# ARM_JTAG_Header.net
KiCad netlist of a schematic drawn in Altium Designer
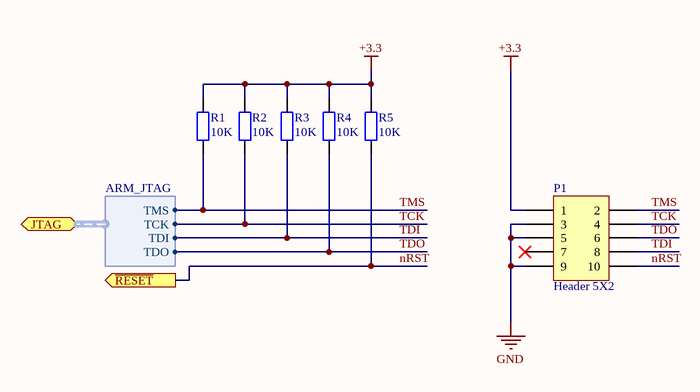
[diagram p0: ARM JTAG Header.SchDoc]

(export (version "E")
  (design (tool "Eeschema 10.0.6"))
  (components
    (comp (ref "P1")
      (value "Header 5X2")
      (footprint "FTSH-105-01-L-DH")
      (description "Header, 5-Pin, Dual row")
      (fields (field (name "PUBLISHER") "Altium Limited"))
      (libsource (lib "Miscellaneous Connectors") (part "Header 5X2"))
    )
    (comp (ref "R1")
      (value "10K")
      (footprint "R0603")
      (description "Resistor")
      (fields (field (name "Comment") "Res"))
      (libsource (lib "Miscellaneous Devices") (part "Res2"))
    )
    (comp (ref "R2")
      (value "10K")
      (footprint "R0603")
      (description "Resistor")
      (fields (field (name "Comment") "Res"))
      (libsource (lib "Miscellaneous Devices") (part "Res2"))
    )
    (comp (ref "R3")
      (value "10K")
      (footprint "R0603")
      (description "Resistor")
      (fields (field (name "Comment") "Res"))
      (libsource (lib "Miscellaneous Devices") (part "Res2"))
    )
    (comp (ref "R4")
      (value "10K")
      (footprint "R0603")
      (description "Resistor")
      (fields (field (name "Comment") "Res"))
      (libsource (lib "Miscellaneous Devices") (part "Res2"))
    )
    (comp (ref "R5")
      (value "10K")
      (footprint "R0603")
      (description "Resistor")
      (fields (field (name "Comment") "Res"))
      (libsource (lib "Miscellaneous Devices") (part "Res2"))
    )
  )
  (nets
    (net (code "2") (name "+3.3") (class "Default")
      (node (ref "P1") (pin "1") (pinfunction "1_1") (pintype "passive"))
      (node (ref "R1") (pin "2") (pinfunction "2_2") (pintype "passive"))
      (node (ref "R2") (pin "2") (pinfunction "2_2") (pintype "passive"))
      (node (ref "R3") (pin "2") (pinfunction "2_2") (pintype "passive"))
      (node (ref "R4") (pin "2") (pinfunction "2_2") (pintype "passive"))
      (node (ref "R5") (pin "2") (pinfunction "2_2") (pintype "passive"))
    )
    (net (code "3") (name "/TCK") (class "Default")
      (node (ref "P1") (pin "4") (pinfunction "4_4") (pintype "passive"))
      (node (ref "R2") (pin "1") (pinfunction "1_1") (pintype "passive"))
    )
    (net (code "4") (name "/TDI") (class "Default")
      (node (ref "P1") (pin "8") (pinfunction "8_8") (pintype "passive"))
      (node (ref "R3") (pin "1") (pinfunction "1_1") (pintype "passive"))
    )
    (net (code "5") (name "/TDO") (class "Default")
      (node (ref "P1") (pin "6") (pinfunction "6_6") (pintype "passive"))
      (node (ref "R4") (pin "1") (pinfunction "1_1") (pintype "passive"))
    )
    (net (code "6") (name "/TMS") (class "Default")
      (node (ref "P1") (pin "2") (pinfunction "2_2") (pintype "passive"))
      (node (ref "R1") (pin "1") (pinfunction "1_1") (pintype "passive"))
    )
    (net (code "7") (name "/nRST") (class "Default")
      (node (ref "P1") (pin "10") (pinfunction "10_10") (pintype "passive"))
      (node (ref "R5") (pin "1") (pinfunction "1_1") (pintype "passive"))
    )
    (net (code "9") (name "GND") (class "Default")
      (node (ref "P1") (pin "3") (pinfunction "3_3") (pintype "passive"))
      (node (ref "P1") (pin "5") (pinfunction "5_5") (pintype "passive"))
      (node (ref "P1") (pin "9") (pinfunction "9_9") (pintype "passive"))
    )
    (net (code "10") (name "unconnected-(P1-Pad7)") (class "Default")
      (node (ref "P1") (pin "7") (pinfunction "7_7") (pintype "passive+no_connect"))
    )
  )
)
